# driver.net
KiCad netlist of a schematic drawn in Altium Designer
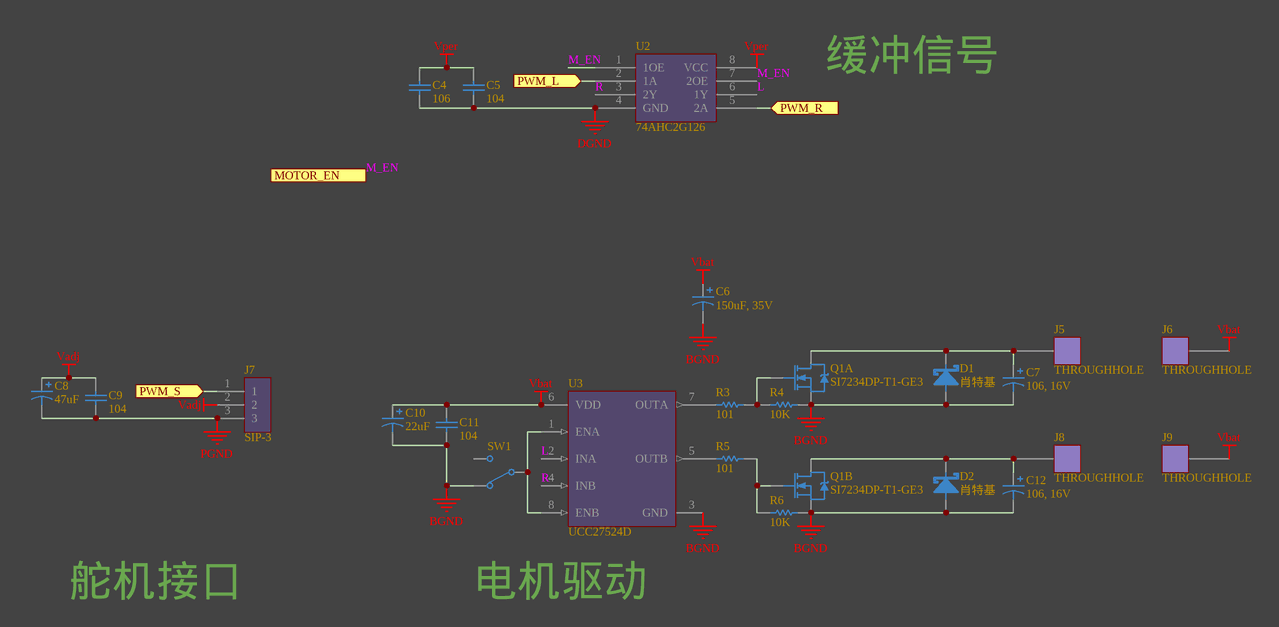
[diagram p0: driver.SchDoc]

(export (version "E")
  (design (tool "Eeschema 10.0.6"))
  (components
    (comp (ref "C4")
      (value "106")
      (footprint "C0603")
      (description "Capacitor")
      (fields (field (name "PUBLISHER") "Altium Limited"))
      (libsource (lib "iMag") (part "电容"))
    )
    (comp (ref "C5")
      (value "104")
      (footprint "C0402")
      (description "Capacitor")
      (fields (field (name "PUBLISHER") "Altium Limited"))
      (libsource (lib "iMag") (part "电容"))
    )
    (comp (ref "C6")
      (value "150uF, 35V")
      (footprint "贴片电解 10*10.5")
      (description "Polarized Capacitor (Axial)")
      (fields (field (name "PUBLISHER") "Altium Limited"))
      (libsource (lib "iMag") (part "电解电容"))
    )
    (comp (ref "C7")
      (value "106, 16V")
      (footprint "贴片电解 6.3*5.4")
      (description "Polarized Capacitor (Axial)")
      (fields (field (name "PUBLISHER") "Altium Limited"))
      (libsource (lib "iMag") (part "电解电容"))
    )
    (comp (ref "C8")
      (value "47uF")
      (footprint "贴片电解 6.3*5.4")
      (description "Polarized Capacitor (Axial)")
      (fields (field (name "PUBLISHER") "Altium Limited"))
      (libsource (lib "iMag") (part "电解电容"))
    )
    (comp (ref "C9")
      (value "104")
      (footprint "C0402")
      (description "Capacitor")
      (fields (field (name "PUBLISHER") "Altium Limited"))
      (libsource (lib "iMag") (part "电容"))
    )
    (comp (ref "C10")
      (value "22uF")
      (footprint "贴片电解 4*5.4")
      (description "Polarized Capacitor (Axial)")
      (fields (field (name "PUBLISHER") "Altium Limited"))
      (libsource (lib "iMag") (part "电解电容"))
    )
    (comp (ref "C11")
      (value "104")
      (footprint "C0402")
      (description "Capacitor")
      (fields (field (name "PUBLISHER") "Altium Limited"))
      (libsource (lib "iMag") (part "电容"))
    )
    (comp (ref "C12")
      (value "106, 16V")
      (footprint "贴片电解 6.3*5.4")
      (description "Polarized Capacitor (Axial)")
      (fields (field (name "PUBLISHER") "Altium Limited"))
      (libsource (lib "iMag") (part "电解电容"))
    )
    (comp (ref "D1")
      (value "肖特基")
      (footprint "SOD-123F")
      (description "Schottky Diode")
      (libsource (lib "iMag") (part "肖特基"))
    )
    (comp (ref "D2")
      (value "肖特基")
      (footprint "SOD-123F")
      (description "Schottky Diode")
      (libsource (lib "iMag") (part "肖特基"))
    )
    (comp (ref "J5") (value "THROUGHHOLE") (footprint "MOTOR") (libsource (lib "iMag") (part "MOTOR")))
    (comp (ref "J6") (value "THROUGHHOLE") (footprint "MOTOR") (libsource (lib "") (part "MOTOR_1")))
    (comp (ref "J7") (value "SIP-3") (footprint "2.54排针1X3") (libsource (lib "iMag") (part "SIP-3")))
    (comp (ref "J8") (value "THROUGHHOLE") (footprint "MOTOR") (libsource (lib "iMag") (part "MOTOR")))
    (comp (ref "J9") (value "THROUGHHOLE") (footprint "MOTOR") (libsource (lib "") (part "MOTOR_1")))
    (comp (ref "Q1")
      (value "SI7234DP-T1-GE3")
      (footprint "DFN-8EP2")
      (description "CQ-BS170")
      (libsource (lib "iMag") (part "N沟道MOSFET"))
    )
    (comp (ref "R3")
      (value "101")
      (footprint "R0603")
      (description "Resistor")
      (fields (field (name "PUBLISHER") "Altium Limited"))
      (libsource (lib "iMag") (part "电阻"))
    )
    (comp (ref "R4")
      (value "10K")
      (footprint "R0402")
      (description "Resistor")
      (fields (field (name "PUBLISHER") "Altium Limited"))
      (libsource (lib "iMag") (part "电阻"))
    )
    (comp (ref "R5")
      (value "101")
      (footprint "R0603")
      (description "Resistor")
      (fields (field (name "PUBLISHER") "Altium Limited"))
      (libsource (lib "iMag") (part "电阻"))
    )
    (comp (ref "R6")
      (value "10K")
      (footprint "R0402")
      (description "Resistor")
      (fields (field (name "PUBLISHER") "Altium Limited"))
      (libsource (lib "iMag") (part "电阻"))
    )
    (comp (ref "SW1")
      (value "K3-1235S-K1")
      (footprint "K3-1235S-K1")
      (description "Switch")
      (libsource (lib "iMag") (part "单刀双掷"))
    )
    (comp (ref "U2") (value "74AHC2G126") (footprint "VSSOP-8") (libsource (lib "iMag") (part "74126")))
    (comp (ref "U3")
      (value "UCC27524D")
      (footprint "TSSOP-8EP")
      (description "No Description Available")
      (fields
        (field (name "PARTNUMBER") "UCC27524DR")
        (field (name "MANUFACTURER") "Texas Instruments")
        (field (name "COPYRIGHT") "Copyright (C) 2018 Accelerated Designs. All rights reserved")
      )
      (libsource (lib "iMag") (part "UCC27524D"))
    )
  )
  (nets
    (net (code "1") (name "/L") (class "Default")
      (node (ref "U2") (pin "6") (pinfunction "1Y_6") (pintype "passive"))
      (node (ref "U3") (pin "2") (pinfunction "INA_2") (pintype "input"))
    )
    (net (code "2") (name "/M_EN") (class "Default")
      (node (ref "U2") (pin "1") (pinfunction "1OE_1") (pintype "passive"))
      (node (ref "U2") (pin "7") (pinfunction "2OE_7") (pintype "passive"))
    )
    (net (code "3") (name "/PWM_L") (class "Default")
      (node (ref "U2") (pin "2") (pinfunction "1A_2") (pintype "passive"))
    )
    (net (code "4") (name "/PWM_R") (class "Default")
      (node (ref "U2") (pin "5") (pinfunction "2A_5") (pintype "passive"))
    )
    (net (code "5") (name "/PWM_S") (class "Default")
      (node (ref "J7") (pin "1") (pinfunction "1_1") (pintype "passive"))
    )
    (net (code "6") (name "/R") (class "Default")
      (node (ref "U2") (pin "3") (pinfunction "2Y_3") (pintype "passive"))
      (node (ref "U3") (pin "4") (pinfunction "INB_4") (pintype "input"))
    )
    (net (code "7") (name "BGND") (class "Default")
      (node (ref "C10") (pin "2") (pinfunction "2_2") (pintype "passive"))
      (node (ref "C11") (pin "1") (pinfunction "1_1") (pintype "passive"))
      (node (ref "C12") (pin "2") (pinfunction "2_2") (pintype "passive"))
      (node (ref "C6") (pin "2") (pinfunction "2_2") (pintype "passive"))
      (node (ref "C7") (pin "2") (pinfunction "2_2") (pintype "passive"))
      (node (ref "D1") (pin "1") (pinfunction "A_1") (pintype "passive"))
      (node (ref "D2") (pin "1") (pinfunction "A_1") (pintype "passive"))
      (node (ref "Q1") (pin "1") (pinfunction "S_1") (pintype "passive"))
      (node (ref "Q1") (pin "3") (pinfunction "S_3") (pintype "passive"))
      (node (ref "R4") (pin "1") (pinfunction "1_1") (pintype "passive"))
      (node (ref "R6") (pin "1") (pinfunction "1_1") (pintype "passive"))
      (node (ref "SW1") (pin "1") (pinfunction "1_1") (pintype "passive"))
      (node (ref "U3") (pin "3") (pinfunction "GND_3") (pintype "power_in"))
    )
    (net (code "8") (name "DGND") (class "Default")
      (node (ref "C4") (pin "1") (pinfunction "1_1") (pintype "passive"))
      (node (ref "C5") (pin "1") (pinfunction "1_1") (pintype "passive"))
      (node (ref "U2") (pin "4") (pinfunction "GND_4") (pintype "passive"))
    )
    (net (code "9") (name "Net-(D1-K)") (class "Default")
      (node (ref "C7") (pin "1") (pinfunction "1_1") (pintype "passive"))
      (node (ref "D1") (pin "2") (pinfunction "K_2") (pintype "passive"))
      (node (ref "J5") (pin "1") (pinfunction "1_1") (pintype "passive"))
      (node (ref "Q1") (pin "6") (pinfunction "D_6") (pintype "passive"))
    )
    (net (code "10") (name "Net-(D2-K)") (class "Default")
      (node (ref "C12") (pin "1") (pinfunction "1_1") (pintype "passive"))
      (node (ref "D2") (pin "2") (pinfunction "K_2") (pintype "passive"))
      (node (ref "J8") (pin "1") (pinfunction "1_1") (pintype "passive"))
      (node (ref "Q1") (pin "5") (pinfunction "D_5") (pintype "passive"))
    )
    (net (code "11") (name "Net-(Q1A-G)") (class "Default")
      (node (ref "Q1") (pin "2") (pinfunction "G_2") (pintype "passive"))
      (node (ref "R3") (pin "1") (pinfunction "1_1") (pintype "passive"))
      (node (ref "R4") (pin "2") (pinfunction "2_2") (pintype "passive"))
    )
    (net (code "12") (name "Net-(Q1B-G)") (class "Default")
      (node (ref "Q1") (pin "4") (pinfunction "G_4") (pintype "passive"))
      (node (ref "R5") (pin "1") (pinfunction "1_1") (pintype "passive"))
      (node (ref "R6") (pin "2") (pinfunction "2_2") (pintype "passive"))
    )
    (net (code "13") (name "Net-(U3-ENA)") (class "Default")
      (node (ref "SW1") (pin "2") (pinfunction "2_2") (pintype "passive"))
      (node (ref "U3") (pin "1") (pinfunction "ENA_1") (pintype "input"))
      (node (ref "U3") (pin "8") (pinfunction "ENB_8") (pintype "input"))
    )
    (net (code "14") (name "Net-(U3-OUTA)") (class "Default")
      (node (ref "R3") (pin "2") (pinfunction "2_2") (pintype "passive"))
      (node (ref "U3") (pin "7") (pinfunction "OUTA_7") (pintype "output"))
    )
    (net (code "15") (name "Net-(U3-OUTB)") (class "Default")
      (node (ref "R5") (pin "2") (pinfunction "2_2") (pintype "passive"))
      (node (ref "U3") (pin "5") (pinfunction "OUTB_5") (pintype "output"))
    )
    (net (code "16") (name "PGND") (class "Default")
      (node (ref "C8") (pin "2") (pinfunction "2_2") (pintype "passive"))
      (node (ref "C9") (pin "1") (pinfunction "1_1") (pintype "passive"))
      (node (ref "J7") (pin "3") (pinfunction "3_3") (pintype "passive"))
    )
    (net (code "17") (name "Vadj") (class "Default")
      (node (ref "C8") (pin "1") (pinfunction "1_1") (pintype "passive"))
      (node (ref "C9") (pin "2") (pinfunction "2_2") (pintype "passive"))
      (node (ref "J7") (pin "2") (pinfunction "2_2") (pintype "passive"))
    )
    (net (code "18") (name "Vbat") (class "Default")
      (node (ref "C10") (pin "1") (pinfunction "1_1") (pintype "passive"))
      (node (ref "C11") (pin "2") (pinfunction "2_2") (pintype "passive"))
      (node (ref "C6") (pin "1") (pinfunction "1_1") (pintype "passive"))
      (node (ref "J6") (pin "1") (pinfunction "1_1") (pintype "passive"))
      (node (ref "J9") (pin "1") (pinfunction "1_1") (pintype "passive"))
      (node (ref "U3") (pin "6") (pinfunction "VDD_6") (pintype "power_in"))
    )
    (net (code "19") (name "Vper") (class "Default")
      (node (ref "C4") (pin "2") (pinfunction "2_2") (pintype "passive"))
      (node (ref "C5") (pin "2") (pinfunction "2_2") (pintype "passive"))
      (node (ref "U2") (pin "8") (pinfunction "VCC_8") (pintype "passive"))
    )
    (net (code "20") (name "unconnected-(SW1-Pad3)") (class "Default")
      (node (ref "SW1") (pin "3") (pinfunction "3_3") (pintype "passive"))
    )
  )
)
